# Sheet1.net
KiCad netlist of a schematic drawn in Altium Designer
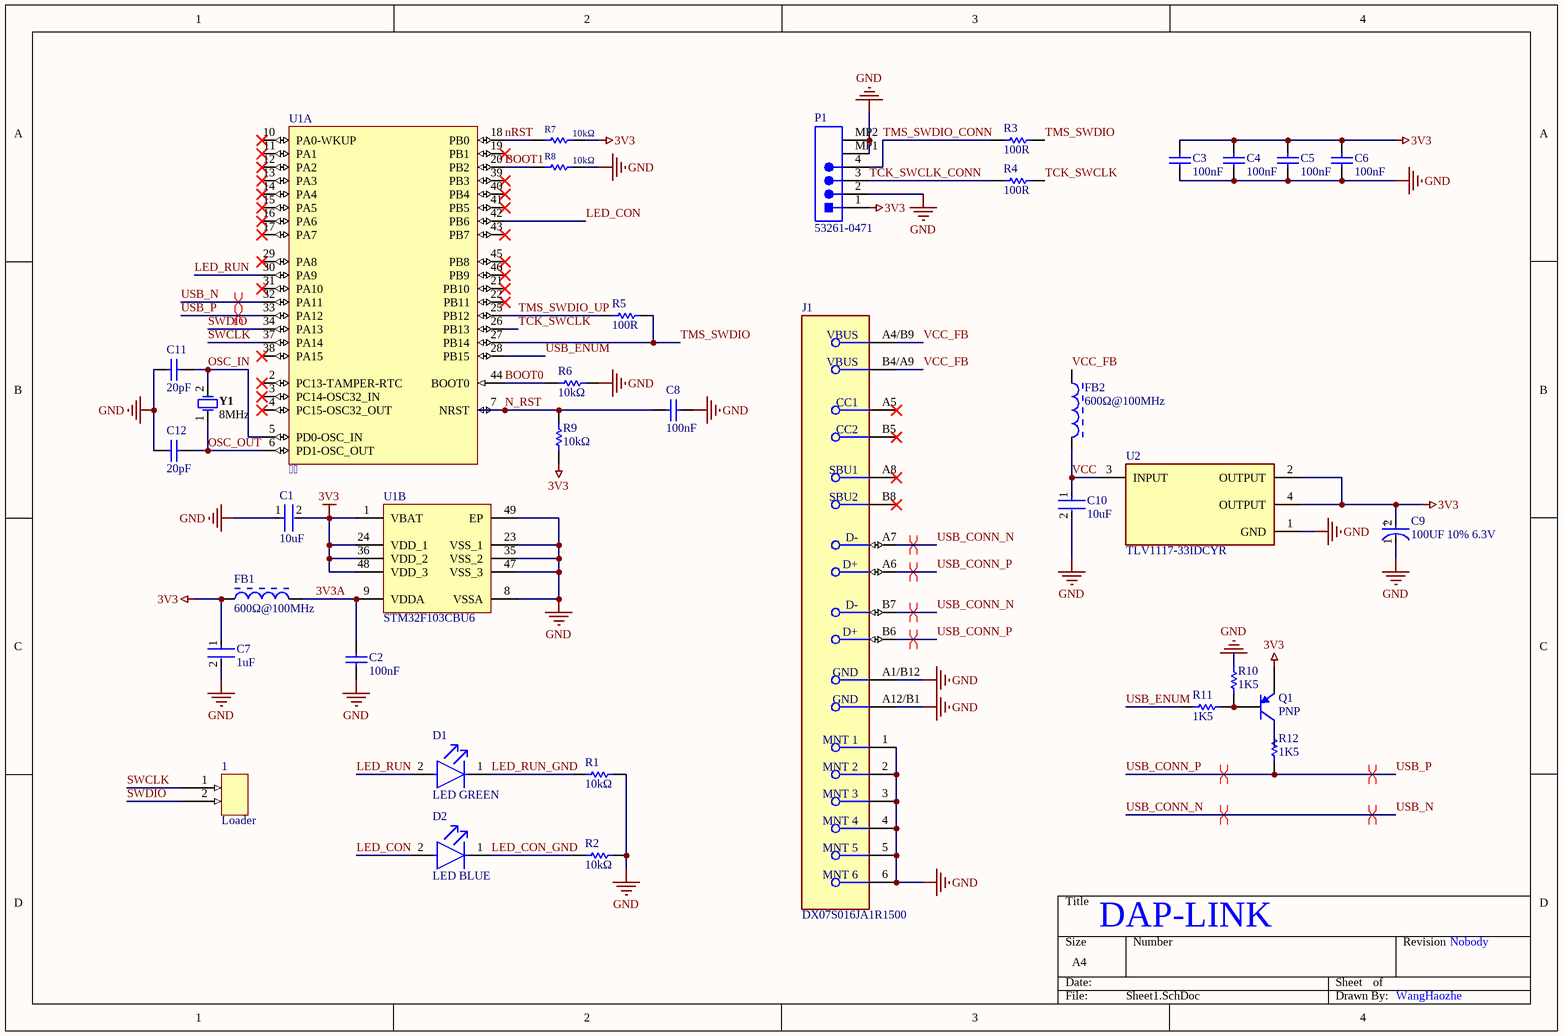
[diagram p0: Sheet1.SchDoc]

(export (version "E")
  (design (tool "Eeschema 10.0.6"))
  (components
    (comp (ref "1") (value "Loader") (footprint "Loader") (libsource (lib "Loader") (part "Loader")))
    (comp (ref "C1")
      (value "10uF")
      (footprint "FP-CL10-IPC_C")
      (description "Cap Ceramic 10uF 25V X5R ±20% Pad SMD 0603 +85°C T/R")
      (fields (field (name "TOLERANCE") "20%"))
      (libsource (lib "Altium Content Vault") (part "b4654b650e69147ec39a6b967a45e02"))
    )
    (comp (ref "C2")
      (value "100nF")
      (footprint "CAPC1050X55X23ML05T13")
      (description "Chip Capacitor, 100 nF, +/- 10%, 16 V, -55 to 125 degC, 0402 (1005 Metric), RoHS, Tape and Reel")
      (fields (field (name "MANUFACTURER") "Samsung Electro-Mechanics"))
      (libsource (lib "Altium Content Vault") (part "CAP-NP-2"))
    )
    (comp (ref "C3")
      (value "100nF")
      (footprint "CAPC1050X55X23ML05T13")
      (description "Chip Capacitor, 100 nF, +/- 10%, 16 V, -55 to 125 degC, 0402 (1005 Metric), RoHS, Tape and Reel")
      (fields (field (name "MANUFACTURER") "Samsung Electro-Mechanics"))
      (libsource (lib "Altium Content Vault") (part "CAP-NP-2"))
    )
    (comp (ref "C4")
      (value "100nF")
      (footprint "CAPC1050X55X23ML05T13")
      (description "Chip Capacitor, 100 nF, +/- 10%, 16 V, -55 to 125 degC, 0402 (1005 Metric), RoHS, Tape and Reel")
      (fields (field (name "MANUFACTURER") "Samsung Electro-Mechanics"))
      (libsource (lib "Altium Content Vault") (part "CAP-NP-2"))
    )
    (comp (ref "C5")
      (value "100nF")
      (footprint "CAPC1050X55X23ML05T13")
      (description "Chip Capacitor, 100 nF, +/- 10%, 16 V, -55 to 125 degC, 0402 (1005 Metric), RoHS, Tape and Reel")
      (fields (field (name "MANUFACTURER") "Samsung Electro-Mechanics"))
      (libsource (lib "Altium Content Vault") (part "CAP-NP-2"))
    )
    (comp (ref "C6")
      (value "100nF")
      (footprint "CAPC1050X55X23ML05T13")
      (description "Chip Capacitor, 100 nF, +/- 10%, 16 V, -55 to 125 degC, 0402 (1005 Metric), RoHS, Tape and Reel")
      (fields (field (name "MANUFACTURER") "Samsung Electro-Mechanics"))
      (libsource (lib "Altium Content Vault") (part "CAP-NP-2"))
    )
    (comp (ref "C7")
      (value "1uF")
      (footprint "FP-CL542-IPC_C")
      (description "Cap Ceramic 1uF 25V X5R ±10% SMD 0402 +85°C Paper T/R")
      (fields (field (name "TOLERANCE") "10%"))
      (libsource (lib "Altium Content Vault") (part "b4654b650e69147ec39a6b967a45e02"))
    )
    (comp (ref "C8")
      (value "100nF")
      (footprint "CAPC1050X55X23ML05T13")
      (description "Chip Capacitor, 100 nF, +/- 10%, 16 V, -55 to 125 degC, 0402 (1005 Metric), RoHS, Tape and Reel")
      (fields (field (name "MANUFACTURER") "Samsung Electro-Mechanics"))
      (libsource (lib "Altium Content Vault") (part "CAP-NP-2"))
    )
    (comp (ref "C9")
      (value "100UF 10% 6.3V")
      (footprint "FP-TAJB-MFG")
      (description "100uF 6.3V  ±10% 1.7Ω 1210  SMD Tantalum Capacitor")
      (fields (field (name "TOLERANCE") "10%") (field (name "VOLTAGE") "6.3V"))
      (libsource (lib "Altium Content Vault") (part "203bc49f2ac43e59fd269a8c329ed05"))
    )
    (comp (ref "C10")
      (value "10uF")
      (footprint "FP-CL10-IPC_C")
      (description "Cap Ceramic 10uF 25V X5R ±20% Pad SMD 0603 +85°C T/R")
      (fields (field (name "TOLERANCE") "20%"))
      (libsource (lib "Altium Content Vault") (part "b4654b650e69147ec39a6b967a45e02"))
    )
    (comp (ref "C11")
      (value "20pF")
      (footprint "CAPC1608X90X30LL10T20")
      (description "Chip Capacitor, 20 pF, +/- 5%, 50 V, -55 to 85 degC, 0603 (1608 Metric), RoHS, Tape and Reel")
      (fields (field (name "MANUFACTURER") "Samsung Electro-Mechanics"))
      (libsource (lib "Altium Content Vault") (part "CAP-NP-2"))
    )
    (comp (ref "C12")
      (value "20pF")
      (footprint "CAPC1608X90X30LL10T20")
      (description "Chip Capacitor, 20 pF, +/- 5%, 50 V, -55 to 85 degC, 0603 (1608 Metric), RoHS, Tape and Reel")
      (fields (field (name "MANUFACTURER") "Samsung Electro-Mechanics"))
      (libsource (lib "Altium Content Vault") (part "CAP-NP-2"))
    )
    (comp (ref "D1")
      (value "LED GREEN")
      (footprint "FP-LTST-C190GKT-MFG")
      (description "LED GREEN CLEAR CHIP SMD")
      (fields (field (name "VOLTAGE") "2V"))
      (libsource (lib "Altium Content Vault") (part "8706943c75ba83719d021d2fdc84c58"))
    )
    (comp (ref "D2")
      (value "LED BLUE")
      (footprint "FP-LTST-C191TBKT-MFG")
      (description "LED BLUE CLEAR CHIP SMD")
      (libsource (lib "Altium Content Vault") (part "8706943c75ba83719d021d2fdc84c58"))
    )
    (comp (ref "FB1")
      (value "600Ω@100MHz")
      (footprint "MURA-BLM18-F-H1-CHIP-2_V")
      (fields (field (name "MANUFACTURER") "Murata") (field (name "PARTNUMBER") "BLM18AG601SN1D"))
      (libsource (lib "Altium Content Vault") (part "MURA-FB-2"))
    )
    (comp (ref "FB2")
      (value "600Ω@100MHz")
      (footprint "MURA-BLM18-F-H1-CHIP-2_V")
      (fields (field (name "MANUFACTURER") "Murata") (field (name "PARTNUMBER") "BLM18AG601SN1D"))
      (libsource (lib "Altium Content Vault") (part "MURA-FB-2"))
    )
    (comp (ref "J1")
      (value "DX07S016JA1R1500")
      (footprint "FP-DX07S016JA1R1500-MFG")
      (description "CONN RCP USB2.0 TYP C 24P SMD RA")
      (libsource (lib "Altium Content Vault") (part "7f3e9989102a0f22bff9cb010881d34"))
    )
    (comp (ref "P1")
      (value "53261-0471")
      (footprint "MOLEX-53261-0471_V")
      (description "Male Header, Pitch 1.25 mm, 1 x 4 Position, Height 3.4 mm, -40 to 85 degC, RoHS, Tape and Reel")
      (fields (field (name "MANUFACTURER") "Molex"))
      (libsource (lib "Altium Content Vault") (part "CN-1P-2M-R4_A"))
    )
    (comp (ref "Q1")
      (value "PNP")
      (footprint "INF-SOT23_N")
      (description "PNP Silicon Switching Transistor, 40 V VCEO, 200 mA IC, SOT23, Reel, Green")
      (fields (field (name "MANUFACTURER") "Infineon") (field (name "PARTNUMBER") "SMBT3906"))
      (libsource (lib "Altium Content Vault") (part "INF-BJTPNP-BEC-3"))
    )
    (comp (ref "R1")
      (value "10kΩ")
      (footprint "RESC1005X40X25NL05T05")
      (fields (field (name "MANUFACTURER") "Vishay Dale") (field (name "PART NUMBER") "CRCW040210K0FKED"))
      (libsource (lib "Altium Content Vault") (part "RES"))
    )
    (comp (ref "R2")
      (value "10kΩ")
      (footprint "RESC1005X40X25NL05T05")
      (fields (field (name "MANUFACTURER") "Vishay Dale") (field (name "PART NUMBER") "CRCW040210K0FKED"))
      (libsource (lib "Altium Content Vault") (part "RES"))
    )
    (comp (ref "R3")
      (value "100R")
      (footprint "RESC1608X55X25ML10T15")
      (description "Chip Resistor, 100 Ohm, +/- 1%, 0.1 W, -55 to 155 degC, 0603 (1608 Metric), RoHS, Tape and Reel")
      (fields (field (name "TOLERANCE") "1%") (field (name "MANUFACTURER") "Yageo"))
      (libsource (lib "Altium Content Vault") (part "RES-2"))
    )
    (comp (ref "R4")
      (value "100R")
      (footprint "RESC1608X55X25ML10T15")
      (description "Chip Resistor, 100 Ohm, +/- 1%, 0.1 W, -55 to 155 degC, 0603 (1608 Metric), RoHS, Tape and Reel")
      (fields (field (name "TOLERANCE") "1%") (field (name "MANUFACTURER") "Yageo"))
      (libsource (lib "Altium Content Vault") (part "RES-2"))
    )
    (comp (ref "R5")
      (value "100R")
      (footprint "RESC1608X55X25ML10T15")
      (description "Chip Resistor, 100 Ohm, +/- 1%, 0.1 W, -55 to 155 degC, 0603 (1608 Metric), RoHS, Tape and Reel")
      (fields (field (name "TOLERANCE") "1%") (field (name "MANUFACTURER") "Yageo"))
      (libsource (lib "Altium Content Vault") (part "RES-2"))
    )
    (comp (ref "R6")
      (value "10kΩ")
      (footprint "RESC1005X40X25NL05T05")
      (fields (field (name "MANUFACTURER") "Vishay Dale") (field (name "PART NUMBER") "CRCW040210K0FKED"))
      (libsource (lib "Altium Content Vault") (part "RES"))
    )
    (comp (ref "R7")
      (value "10kΩ")
      (footprint "RESC1005X40X25NL05T05")
      (fields (field (name "MANUFACTURER") "Vishay Dale") (field (name "PART NUMBER") "CRCW040210K0FKED"))
      (libsource (lib "Altium Content Vault") (part "RES"))
    )
    (comp (ref "R8")
      (value "10kΩ")
      (footprint "RESC1005X40X25NL05T05")
      (fields (field (name "MANUFACTURER") "Vishay Dale") (field (name "PART NUMBER") "CRCW040210K0FKED"))
      (libsource (lib "Altium Content Vault") (part "RES"))
    )
    (comp (ref "R9")
      (value "10kΩ")
      (footprint "RESC1005X40X25NL05T05")
      (fields (field (name "MANUFACTURER") "Vishay Dale") (field (name "PART NUMBER") "CRCW040210K0FKED"))
      (libsource (lib "Altium Content Vault") (part "RES"))
    )
    (comp (ref "R10")
      (value "1K5")
      (footprint "RESC1005X40X25ML05T10")
      (fields (field (name "MANUFACTURER") "Yageo / Phycomp") (field (name "PART NUMBER") "RC0402FR-071K5L"))
      (libsource (lib "Altium Content Vault") (part "RES"))
    )
    (comp (ref "R11")
      (value "1K5")
      (footprint "RESC1005X40X25ML05T10")
      (fields (field (name "MANUFACTURER") "Yageo / Phycomp") (field (name "PART NUMBER") "RC0402FR-071K5L"))
      (libsource (lib "Altium Content Vault") (part "RES"))
    )
    (comp (ref "R12")
      (value "1K5")
      (footprint "RESC1005X40X25ML05T10")
      (fields (field (name "MANUFACTURER") "Yageo / Phycomp") (field (name "PART NUMBER") "RC0402FR-071K5L"))
      (libsource (lib "Altium Content Vault") (part "RES"))
    )
    (comp (ref "U1")
      (value "")
      (footprint "STM-UFQFPN48_N")
      (fields (field (name "PARTNUMBER") "STM32F103CBU6"))
      (libsource (lib "Altium Content Vault") (part "MC-ARM-STM32F103X8_B-SQ49"))
    )
    (comp (ref "U2")
      (value "TLV1117-33IDCYR")
      (footprint "FP-DCY0004A-MFG")
      (description "IC REG LIN 3.3V 800MA SOT223-4")
      (fields
        (field (name "MANUFACTURER") "Texas Instruments")
        (field (name "OCTOPART") "https://octopart.com/tlv1117-33idcyr-texas+instruments-669250")
      )
      (libsource (lib "Altium Content Vault") (part "d420fb9686013fb832e66295cdf4acf"))
    )
    (comp (ref "Y1")
      (value "8MHz")
      (footprint "NDK-NX3225GD-8MHZ-STD-CRA-3_V")
      (description "Crystal Unit, 8 MHz, 8 pF, -40 to 150 degC, 2-Pin SMD, RoHS, Tape and Reel")
      (fields (field (name "MANUFACTURER") "NDK"))
      (libsource (lib "Altium Content Vault") (part "XTAL-1-2-2"))
    )
  )
  (nets
    (net (code "1") (name "/3V3A") (class "Default")
      (node (ref "C2") (pin "2") (pinfunction "2_2") (pintype "passive"))
      (node (ref "FB1") (pin "2") (pinfunction "2_2") (pintype "passive"))
      (node (ref "U1") (pin "9") (pinfunction "VDDA_9") (pintype "power_in"))
    )
    (net (code "2") (name "/BOOT0") (class "Default")
      (node (ref "R6") (pin "1") (pinfunction "1_1") (pintype "passive"))
      (node (ref "U1") (pin "44") (pinfunction "BOOT0_44") (pintype "input"))
    )
    (net (code "3") (name "/BOOT1") (class "Default")
      (node (ref "R8") (pin "1") (pinfunction "1_1") (pintype "passive"))
      (node (ref "U1") (pin "20") (pinfunction "PB2_20") (pintype "bidirectional"))
    )
    (net (code "4") (name "/LED_CON") (class "Default")
      (node (ref "D2") (pin "2") (pinfunction "A_2") (pintype "passive"))
      (node (ref "U1") (pin "42") (pinfunction "PB6_42") (pintype "bidirectional"))
    )
    (net (code "5") (name "/LED_CON_GND") (class "Default")
      (node (ref "D2") (pin "1") (pinfunction "C_1") (pintype "passive"))
      (node (ref "R2") (pin "1") (pinfunction "1_1") (pintype "passive"))
    )
    (net (code "6") (name "/LED_RUN") (class "Default")
      (node (ref "D1") (pin "2") (pinfunction "A_2") (pintype "passive"))
      (node (ref "U1") (pin "30") (pinfunction "PA9_30") (pintype "bidirectional"))
    )
    (net (code "7") (name "/LED_RUN_GND") (class "Default")
      (node (ref "D1") (pin "1") (pinfunction "C_1") (pintype "passive"))
      (node (ref "R1") (pin "1") (pinfunction "1_1") (pintype "passive"))
    )
    (net (code "8") (name "/N_RST") (class "Default")
      (node (ref "C8") (pin "1") (pinfunction "1_1") (pintype "passive"))
      (node (ref "R9") (pin "1") (pinfunction "1_1") (pintype "passive"))
      (node (ref "U1") (pin "7") (pinfunction "NRST_7") (pintype "bidirectional"))
    )
    (net (code "9") (name "/OSC_IN") (class "Default")
      (node (ref "C11") (pin "2") (pinfunction "2_2") (pintype "passive"))
      (node (ref "U1") (pin "5") (pinfunction "PD0-OSC_IN_5") (pintype "bidirectional"))
      (node (ref "Y1") (pin "2") (pinfunction "2_2") (pintype "passive"))
    )
    (net (code "10") (name "/OSC_OUT") (class "Default")
      (node (ref "C12") (pin "2") (pinfunction "2_2") (pintype "passive"))
      (node (ref "U1") (pin "6") (pinfunction "PD1-OSC_OUT_6") (pintype "bidirectional"))
      (node (ref "Y1") (pin "1") (pinfunction "1_1") (pintype "passive"))
    )
    (net (code "11") (name "/SWCLK") (class "Default")
      (node (ref "1") (pin "1") (pintype "input"))
      (node (ref "U1") (pin "37") (pinfunction "PA14_37") (pintype "bidirectional"))
    )
    (net (code "12") (name "/SWDIO") (class "Default")
      (node (ref "1") (pin "2") (pintype "input"))
      (node (ref "U1") (pin "34") (pinfunction "PA13_34") (pintype "bidirectional"))
    )
    (net (code "13") (name "/TCK_SWCLK") (class "Default")
      (node (ref "R4") (pin "2") (pinfunction "2_2") (pintype "passive"))
      (node (ref "U1") (pin "26") (pinfunction "PB13_26") (pintype "bidirectional"))
    )
    (net (code "14") (name "/TCK_SWCLK_CONN") (class "Default")
      (node (ref "P1") (pin "3") (pinfunction "3_3") (pintype "passive"))
      (node (ref "R4") (pin "1") (pinfunction "1_1") (pintype "passive"))
    )
    (net (code "15") (name "/TMS_SWDIO") (class "Default")
      (node (ref "R3") (pin "2") (pinfunction "2_2") (pintype "passive"))
      (node (ref "R5") (pin "2") (pinfunction "2_2") (pintype "passive"))
      (node (ref "U1") (pin "27") (pinfunction "PB14_27") (pintype "bidirectional"))
    )
    (net (code "16") (name "/TMS_SWDIO_CONN") (class "Default")
      (node (ref "P1") (pin "4") (pinfunction "4_4") (pintype "passive"))
      (node (ref "R3") (pin "1") (pinfunction "1_1") (pintype "passive"))
    )
    (net (code "17") (name "/TMS_SWDIO_UP") (class "Default")
      (node (ref "R5") (pin "1") (pinfunction "1_1") (pintype "passive"))
      (node (ref "U1") (pin "25") (pinfunction "PB12_25") (pintype "bidirectional"))
    )
    (net (code "18") (name "/USB_CONN_N") (class "Default")
      (node (ref "J1") (pin "A7") (pinfunction "D-_A7") (pintype "bidirectional"))
      (node (ref "J1") (pin "B7") (pinfunction "D-_B7") (pintype "bidirectional"))
      (node (ref "U1") (pin "32") (pinfunction "PA11_32") (pintype "bidirectional"))
    )
    (net (code "19") (name "/USB_CONN_P") (class "Default")
      (node (ref "J1") (pin "A6") (pinfunction "D+_A6") (pintype "bidirectional"))
      (node (ref "J1") (pin "B6") (pinfunction "D+_B6") (pintype "bidirectional"))
      (node (ref "R12") (pin "1") (pinfunction "1_1") (pintype "passive"))
      (node (ref "U1") (pin "33") (pinfunction "PA12_33") (pintype "bidirectional"))
    )
    (net (code "20") (name "/USB_ENUM") (class "Default")
      (node (ref "R11") (pin "2") (pinfunction "2_2") (pintype "passive"))
      (node (ref "U1") (pin "28") (pinfunction "PB15_28") (pintype "bidirectional"))
    )
    (net (code "21") (name "/VCC") (class "Default")
      (node (ref "C10") (pin "1") (pinfunction "1_1") (pintype "passive"))
      (node (ref "FB2") (pin "2") (pinfunction "2_2") (pintype "passive"))
      (node (ref "U2") (pin "3") (pinfunction "INPUT_3") (pintype "power_in"))
    )
    (net (code "22") (name "/VCC_FB") (class "Default")
      (node (ref "FB2") (pin "1") (pinfunction "1_1") (pintype "passive"))
      (node (ref "J1") (pin "A4/B9") (pinfunction "VBUS_A4/B9") (pintype "power_in"))
      (node (ref "J1") (pin "B4/A9") (pinfunction "VBUS_B4/A9") (pintype "power_in"))
    )
    (net (code "23") (name "/nRST") (class "Default")
      (node (ref "R7") (pin "1") (pinfunction "1_1") (pintype "passive"))
      (node (ref "U1") (pin "18") (pinfunction "PB0_18") (pintype "bidirectional"))
    )
    (net (code "24") (name "3V3") (class "Default")
      (node (ref "C1") (pin "2") (pinfunction "2_2") (pintype "passive"))
      (node (ref "C3") (pin "2") (pinfunction "2_2") (pintype "passive"))
      (node (ref "C4") (pin "2") (pinfunction "2_2") (pintype "passive"))
      (node (ref "C5") (pin "2") (pinfunction "2_2") (pintype "passive"))
      (node (ref "C6") (pin "2") (pinfunction "2_2") (pintype "passive"))
      (node (ref "C7") (pin "1") (pinfunction "1_1") (pintype "passive"))
      (node (ref "C9") (pin "2") (pinfunction "A_2") (pintype "passive"))
      (node (ref "FB1") (pin "1") (pinfunction "1_1") (pintype "passive"))
      (node (ref "P1") (pin "1") (pinfunction "1_1") (pintype "passive"))
      (node (ref "Q1") (pin "2") (pinfunction "E_2") (pintype "passive"))
      (node (ref "R7") (pin "2") (pinfunction "2_2") (pintype "passive"))
      (node (ref "R9") (pin "2") (pinfunction "2_2") (pintype "passive"))
      (node (ref "U1") (pin "1") (pinfunction "VBAT_1") (pintype "power_in"))
      (node (ref "U1") (pin "24") (pinfunction "VDD_1_24") (pintype "power_in"))
      (node (ref "U1") (pin "36") (pinfunction "VDD_2_36") (pintype "power_in"))
      (node (ref "U1") (pin "48") (pinfunction "VDD_3_48") (pintype "power_in"))
      (node (ref "U2") (pin "2") (pinfunction "OUTPUT_2") (pintype "power_in"))
      (node (ref "U2") (pin "4") (pinfunction "OUTPUT_4") (pintype "power_in"))
    )
    (net (code "25") (name "GND") (class "Default")
      (node (ref "C1") (pin "1") (pinfunction "1_1") (pintype "passive"))
      (node (ref "C10") (pin "2") (pinfunction "2_2") (pintype "passive"))
      (node (ref "C11") (pin "1") (pinfunction "1_1") (pintype "passive"))
      (node (ref "C12") (pin "1") (pinfunction "1_1") (pintype "passive"))
      (node (ref "C2") (pin "1") (pinfunction "1_1") (pintype "passive"))
      (node (ref "C3") (pin "1") (pinfunction "1_1") (pintype "passive"))
      (node (ref "C4") (pin "1") (pinfunction "1_1") (pintype "passive"))
      (node (ref "C5") (pin "1") (pinfunction "1_1") (pintype "passive"))
      (node (ref "C6") (pin "1") (pinfunction "1_1") (pintype "passive"))
      (node (ref "C7") (pin "2") (pinfunction "2_2") (pintype "passive"))
      (node (ref "C8") (pin "2") (pinfunction "2_2") (pintype "passive"))
      (node (ref "C9") (pin "1") (pinfunction "C_1") (pintype "passive"))
      (node (ref "J1") (pin "1") (pinfunction "MNT_1_1") (pintype "passive"))
      (node (ref "J1") (pin "2") (pinfunction "MNT_2_2") (pintype "passive"))
      (node (ref "J1") (pin "3") (pinfunction "MNT_3_3") (pintype "passive"))
      (node (ref "J1") (pin "4") (pinfunction "MNT_4_4") (pintype "passive"))
      (node (ref "J1") (pin "5") (pinfunction "MNT_5_5") (pintype "passive"))
      (node (ref "J1") (pin "6") (pinfunction "MNT_6_6") (pintype "passive"))
      (node (ref "J1") (pin "A1/B12") (pinfunction "GND_A1/B12") (pintype "power_in"))
      (node (ref "J1") (pin "A12/B1") (pinfunction "GND_A12/B1") (pintype "power_in"))
      (node (ref "P1") (pin "2") (pinfunction "2_2") (pintype "passive"))
      (node (ref "P1") (pin "MP1") (pinfunction "MP1_MP1") (pintype "passive"))
      (node (ref "P1") (pin "MP2") (pinfunction "MP2_MP2") (pintype "passive"))
      (node (ref "R1") (pin "2") (pinfunction "2_2") (pintype "passive"))
      (node (ref "R10") (pin "1") (pinfunction "1_1") (pintype "passive"))
      (node (ref "R2") (pin "2") (pinfunction "2_2") (pintype "passive"))
      (node (ref "R6") (pin "2") (pinfunction "2_2") (pintype "passive"))
      (node (ref "R8") (pin "2") (pinfunction "2_2") (pintype "passive"))
      (node (ref "U1") (pin "23") (pinfunction "VSS_1_23") (pintype "power_in"))
      (node (ref "U1") (pin "35") (pinfunction "VSS_2_35") (pintype "power_in"))
      (node (ref "U1") (pin "47") (pinfunction "VSS_3_47") (pintype "power_in"))
      (node (ref "U1") (pin "49") (pinfunction "EP_49") (pintype "power_in"))
      (node (ref "U1") (pin "8") (pinfunction "VSSA_8") (pintype "power_in"))
      (node (ref "U2") (pin "1") (pinfunction "GND_1") (pintype "power_in"))
    )
    (net (code "26") (name "Net-(Q1-B)") (class "Default")
      (node (ref "Q1") (pin "1") (pinfunction "B_1") (pintype "passive"))
      (node (ref "R10") (pin "2") (pinfunction "2_2") (pintype "passive"))
      (node (ref "R11") (pin "1") (pinfunction "1_1") (pintype "passive"))
    )
    (net (code "27") (name "Net-(Q1-C)") (class "Default")
      (node (ref "Q1") (pin "3") (pinfunction "C_3") (pintype "passive"))
      (node (ref "R12") (pin "2") (pinfunction "2_2") (pintype "passive"))
    )
    (net (code "28") (name "unconnected-(J1-CC1-PadA5)") (class "Default")
      (node (ref "J1") (pin "A5") (pinfunction "CC1_A5") (pintype "passive+no_connect"))
    )
    (net (code "29") (name "unconnected-(J1-CC2-PadB5)") (class "Default")
      (node (ref "J1") (pin "B5") (pinfunction "CC2_B5") (pintype "passive+no_connect"))
    )
    (net (code "30") (name "unconnected-(J1-SBU1-PadA8)") (class "Default")
      (node (ref "J1") (pin "A8") (pinfunction "SBU1_A8") (pintype "passive+no_connect"))
    )
    (net (code "31") (name "unconnected-(J1-SBU2-PadB8)") (class "Default")
      (node (ref "J1") (pin "B8") (pinfunction "SBU2_B8") (pintype "passive+no_connect"))
    )
    (net (code "32") (name "unconnected-(U1A-PA0-WKUP-Pad10)") (class "Default")
      (node (ref "U1") (pin "10") (pinfunction "PA0-WKUP_10") (pintype "bidirectional+no_connect"))
    )
    (net (code "33") (name "unconnected-(U1A-PA1-Pad11)") (class "Default")
      (node (ref "U1") (pin "11") (pinfunction "PA1_11") (pintype "bidirectional+no_connect"))
    )
    (net (code "34") (name "unconnected-(U1A-PA2-Pad12)") (class "Default")
      (node (ref "U1") (pin "12") (pinfunction "PA2_12") (pintype "bidirectional+no_connect"))
    )
    (net (code "35") (name "unconnected-(U1A-PA3-Pad13)") (class "Default")
      (node (ref "U1") (pin "13") (pinfunction "PA3_13") (pintype "bidirectional+no_connect"))
    )
    (net (code "36") (name "unconnected-(U1A-PA4-Pad14)") (class "Default")
      (node (ref "U1") (pin "14") (pinfunction "PA4_14") (pintype "bidirectional+no_connect"))
    )
    (net (code "37") (name "unconnected-(U1A-PA5-Pad15)") (class "Default")
      (node (ref "U1") (pin "15") (pinfunction "PA5_15") (pintype "bidirectional+no_connect"))
    )
    (net (code "38") (name "unconnected-(U1A-PA6-Pad16)") (class "Default")
      (node (ref "U1") (pin "16") (pinfunction "PA6_16") (pintype "bidirectional+no_connect"))
    )
    (net (code "39") (name "unconnected-(U1A-PA7-Pad17)") (class "Default")
      (node (ref "U1") (pin "17") (pinfunction "PA7_17") (pintype "bidirectional+no_connect"))
    )
    (net (code "40") (name "unconnected-(U1A-PA8-Pad29)") (class "Default")
      (node (ref "U1") (pin "29") (pinfunction "PA8_29") (pintype "bidirectional+no_connect"))
    )
    (net (code "41") (name "unconnected-(U1A-PA10-Pad31)") (class "Default")
      (node (ref "U1") (pin "31") (pinfunction "PA10_31") (pintype "bidirectional+no_connect"))
    )
    (net (code "42") (name "unconnected-(U1A-PA15-Pad38)") (class "Default")
      (node (ref "U1") (pin "38") (pinfunction "PA15_38") (pintype "bidirectional+no_connect"))
    )
    (net (code "43") (name "unconnected-(U1A-PB1-Pad19)") (class "Default")
      (node (ref "U1") (pin "19") (pinfunction "PB1_19") (pintype "bidirectional+no_connect"))
    )
    (net (code "44") (name "unconnected-(U1A-PB3-Pad39)") (class "Default")
      (node (ref "U1") (pin "39") (pinfunction "PB3_39") (pintype "bidirectional+no_connect"))
    )
    (net (code "45") (name "unconnected-(U1A-PB4-Pad40)") (class "Default")
      (node (ref "U1") (pin "40") (pinfunction "PB4_40") (pintype "bidirectional+no_connect"))
    )
    (net (code "46") (name "unconnected-(U1A-PB5-Pad41)") (class "Default")
      (node (ref "U1") (pin "41") (pinfunction "PB5_41") (pintype "bidirectional+no_connect"))
    )
    (net (code "47") (name "unconnected-(U1A-PB7-Pad43)") (class "Default")
      (node (ref "U1") (pin "43") (pinfunction "PB7_43") (pintype "bidirectional+no_connect"))
    )
    (net (code "48") (name "unconnected-(U1A-PB8-Pad45)") (class "Default")
      (node (ref "U1") (pin "45") (pinfunction "PB8_45") (pintype "bidirectional+no_connect"))
    )
    (net (code "49") (name "unconnected-(U1A-PB9-Pad46)") (class "Default")
      (node (ref "U1") (pin "46") (pinfunction "PB9_46") (pintype "bidirectional+no_connect"))
    )
    (net (code "50") (name "unconnected-(U1A-PB10-Pad21)") (class "Default")
      (node (ref "U1") (pin "21") (pinfunction "PB10_21") (pintype "bidirectional+no_connect"))
    )
    (net (code "51") (name "unconnected-(U1A-PB11-Pad22)") (class "Default")
      (node (ref "U1") (pin "22") (pinfunction "PB11_22") (pintype "bidirectional+no_connect"))
    )
    (net (code "52") (name "unconnected-(U1A-PC13-TAMPER-RTC-Pad2)") (class "Default")
      (node (ref "U1") (pin "2") (pinfunction "PC13-TAMPER-RTC_2") (pintype "bidirectional+no_connect"))
    )
    (net (code "53") (name "unconnected-(U1A-PC14-OSC32_IN-Pad3)") (class "Default")
      (node (ref "U1") (pin "3") (pinfunction "PC14-OSC32_IN_3") (pintype "bidirectional+no_connect"))
    )
    (net (code "54") (name "unconnected-(U1A-PC15-OSC32_OUT-Pad4)") (class "Default")
      (node (ref "U1") (pin "4") (pinfunction "PC15-OSC32_OUT_4") (pintype "bidirectional+no_connect"))
    )
  )
)
